# LDO_Schematic.net
KiCad netlist of a schematic drawn in Altium Designer
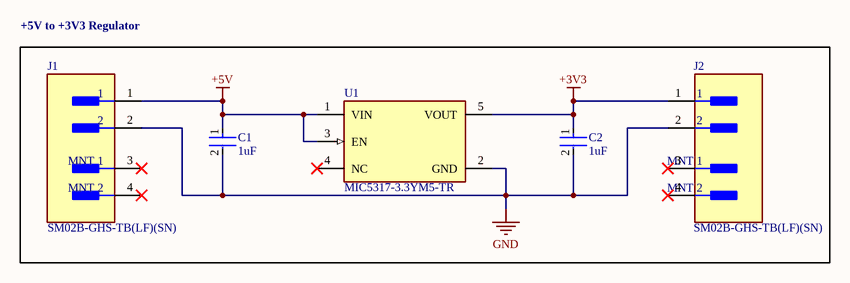
[diagram p0: LDO_Schematic.SchDoc]

(export (version "E")
  (design (tool "Eeschema 10.0.6"))
  (components
    (comp (ref "C1")
      (value "1uF")
      (footprint "FP-CC0805-0_85-MFG")
      (description "CAP CER 1UF 10V X7R 0805")
      (fields
        (field (name "MANUFACTURER PART NUMBER") "CC0805MKX7R6BB105")
        (field (name "OCTOPART") "https://octopart.com/cc0805mkx7r6bb105-yageo-71334590")
      )
      (libsource (lib "Altium Content Vault") (part "11868f565c42a9108669ba33697ecf6"))
    )
    (comp (ref "C2")
      (value "1uF")
      (footprint "FP-CC0805-0_85-MFG")
      (description "CAP CER 1UF 10V X7R 0805")
      (fields
        (field (name "MANUFACTURER PART NUMBER") "CC0805MKX7R6BB105")
        (field (name "OCTOPART") "https://octopart.com/cc0805mkx7r6bb105-yageo-71334590")
      )
      (libsource (lib "Altium Content Vault") (part "11868f565c42a9108669ba33697ecf6"))
    )
    (comp (ref "J1")
      (value "SM02B-GHS-TB(LF)(SN)")
      (footprint "FP-SM02B-GHS-TB_LF_SN-MFG")
      (description "CONN HEADER SMD R/A 2POS 1.25MM")
      (libsource (lib "") (part "56ec3178a87b3978bdc1b3682cd516a_1"))
    )
    (comp (ref "J2")
      (value "SM02B-GHS-TB(LF)(SN)")
      (footprint "FP-SM02B-GHS-TB_LF_SN-MFG")
      (description "CONN HEADER SMD R/A 2POS 1.25MM")
      (libsource (lib "Altium Content Vault") (part "56ec3178a87b3978bdc1b3682cd516a"))
    )
    (comp (ref "U1")
      (value "MIC5317-3.3YM5-TR")
      (footprint "FP-SOT23-5LD-PL-1-MFG")
      (description "IC REG LINEAR 3.3V 150MA SOT23-5")
      (libsource (lib "Altium Content Vault") (part "0a093dae7315cdc977fd108dde87457"))
    )
  )
  (nets
    (net (code "1") (name "+3V3") (class "Default")
      (node (ref "C2") (pin "1") (pinfunction "1_1") (pintype "passive"))
      (node (ref "J2") (pin "1") (pinfunction "1_1") (pintype "passive"))
      (node (ref "U1") (pin "5") (pinfunction "VOUT_5") (pintype "power_in"))
    )
    (net (code "2") (name "+5V") (class "Default")
      (node (ref "C1") (pin "1") (pinfunction "1_1") (pintype "passive"))
      (node (ref "J1") (pin "1") (pinfunction "1_1") (pintype "passive"))
      (node (ref "U1") (pin "1") (pinfunction "VIN_1") (pintype "power_in"))
      (node (ref "U1") (pin "3") (pinfunction "EN_3") (pintype "input"))
    )
    (net (code "3") (name "GND") (class "Default")
      (node (ref "C1") (pin "2") (pinfunction "2_2") (pintype "passive"))
      (node (ref "C2") (pin "2") (pinfunction "2_2") (pintype "passive"))
      (node (ref "J1") (pin "2") (pinfunction "2_2") (pintype "passive"))
      (node (ref "J2") (pin "2") (pinfunction "2_2") (pintype "passive"))
      (node (ref "U1") (pin "2") (pinfunction "GND_2") (pintype "power_in"))
    )
    (net (code "4") (name "unconnected-(J1-MNT_1-Pad3)") (class "Default")
      (node (ref "J1") (pin "3") (pinfunction "MNT_1_3") (pintype "passive+no_connect"))
    )
    (net (code "5") (name "unconnected-(J1-MNT_2-Pad4)") (class "Default")
      (node (ref "J1") (pin "4") (pinfunction "MNT_2_4") (pintype "passive+no_connect"))
    )
    (net (code "6") (name "unconnected-(J2-MNT_1-Pad3)") (class "Default")
      (node (ref "J2") (pin "3") (pinfunction "MNT_1_3") (pintype "passive+no_connect"))
    )
    (net (code "7") (name "unconnected-(J2-MNT_2-Pad4)") (class "Default")
      (node (ref "J2") (pin "4") (pinfunction "MNT_2_4") (pintype "passive+no_connect"))
    )
    (net (code "8") (name "unconnected-(U1-NC-Pad4)") (class "Default")
      (node (ref "U1") (pin "4") (pinfunction "NC_4") (pintype "passive+no_connect"))
    )
  )
)
